# SPEED-CONTROLER.net
KiCad netlist of a schematic drawn in Altium Designer
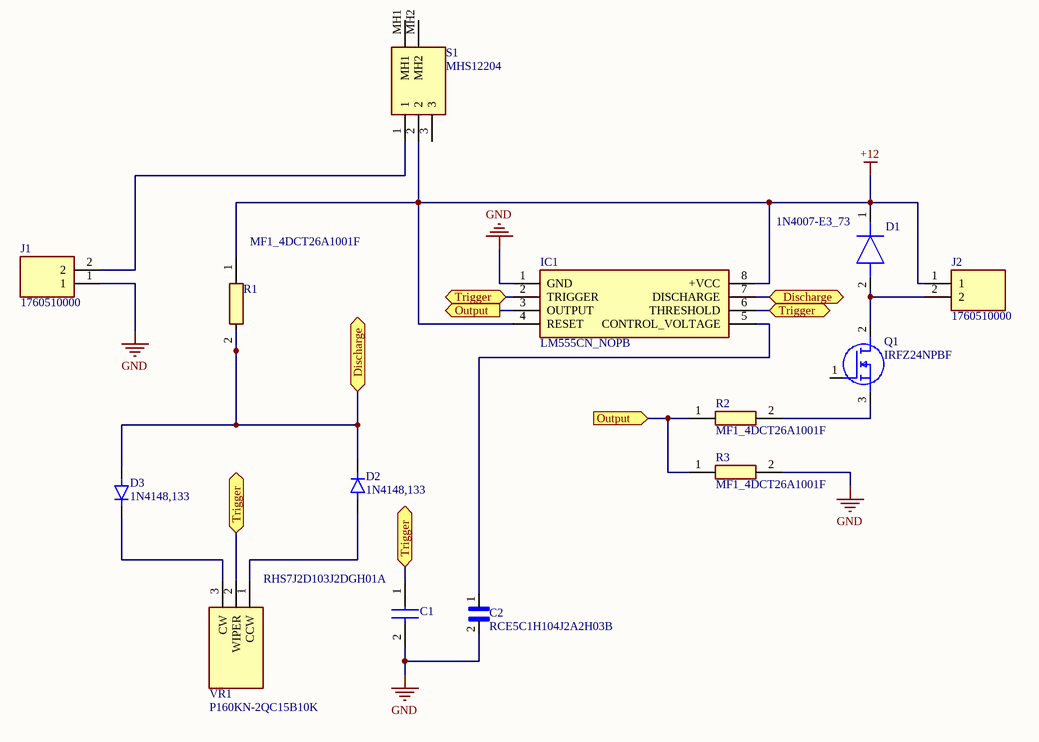
[diagram p0: SPEED-CONTROLER.SchDoc]

(export (version "E")
  (design (tool "Eeschema 10.0.6"))
  (components
    (comp (ref "C1")
      (value "RHS7J2D103J2DGH01A")
      (footprint "SamacSys:RHS7J2D103J2DGH01A")
      (description "Capacitor")
      (fields (field (name "MOUSER PART NUMBER") "81-RHS7J2D103J2DGH1A"))
      (libsource (lib "*") (part "RHS7J2D103J2DGH01A"))
    )
    (comp (ref "C2")
      (value "RCE5C1H104J2A2H03B")
      (footprint "CAP_RCE5C1H104J2A2H03B")
      (description "Multilayer Ceramic Capacitors MLCC - Leaded")
      (libsource (lib "RCE5C1H104J2A2H03B") (part "RCE5C1H104J2A2H03B"))
    )
    (comp (ref "D1")
      (value "1N4007-E3_73")
      (footprint "SamacSys:DIOAD1405W86L465D235")
      (description "Diode")
      (fields
        (field (name "MANUFACTURER_PART_NUMBER") "1N4007-E3/73")
        (field (name "MOUSER PART NUMBER") "625-1N4007-E3/73")
      )
      (libsource (lib "*") (part "1N4007-E3_73"))
    )
    (comp (ref "D2")
      (value "1N4148,133")
      (footprint "DIOAD753W49L380D172B")
      (description "Diode Standard 75V 200mA Surface Mount SOD-523F")
      (fields (field (name "MF") "ON Semiconductor") (field (name "MP") "1N4148"))
      (libsource (lib "1N4148") (part "1N4148"))
    )
    (comp (ref "D3")
      (value "1N4148,133")
      (footprint "DIOAD753W49L380D172B")
      (description "Diode Standard 75V 200mA Surface Mount SOD-523F")
      (fields (field (name "MF") "ON Semiconductor") (field (name "MP") "1N4148"))
      (libsource (lib "1N4148") (part "1N4148"))
    )
    (comp (ref "IC1")
      (value "LM555CN_NOPB")
      (footprint "SamacSys:DIP794W53P254L959H508Q8N")
      (description "Integrated Circuit")
      (fields
        (field (name "MANUFACTURER_PART_NUMBER") "LM555CN/NOPB")
        (field (name "MOUSER PART NUMBER") "926-LM555CN/NOPB")
      )
      (libsource (lib "*") (part "LM555CN_NOPB"))
    )
    (comp (ref "J1")
      (value "1760510000")
      (footprint "SamacSys:1760510000")
      (description "Connector")
      (fields (field (name "MOUSER PART NUMBER") "470-1760510000"))
      (libsource (lib "") (part "1760510000_1"))
    )
    (comp (ref "J2")
      (value "1760510000")
      (footprint "SamacSys:1760510000")
      (description "Connector")
      (fields (field (name "MOUSER PART NUMBER") "470-1760510000"))
      (libsource (lib "SamacSys") (part "1760510000"))
    )
    (comp (ref "Q1")
      (value "IRFZ24NPBF")
      (footprint "SamacSys:TO254P469X1042X1967-3P")
      (description "MOSFET (N-Channel)")
      (fields (field (name "MOUSER PART NUMBER") "942-IRFZ24NPBF"))
      (libsource (lib "*") (part "IRFZ24NPBF"))
    )
    (comp (ref "R1")
      (value "MF1_4DCT26A1001F")
      (footprint "SamacSys:RESAD1630W60L710D230")
      (description "Resistor")
      (fields
        (field (name "MANUFACTURER_PART_NUMBER") "MF1/4DCT26A1001F")
        (field (name "MOUSER PART NUMBER") "660-MF1/4DCT26A1001F")
      )
      (libsource (lib "*") (part "MF1_4DCT26A1001F"))
    )
    (comp (ref "R2")
      (value "MF1_4DCT26A1001F")
      (footprint "SamacSys:RESAD1630W60L710D230")
      (description "Resistor")
      (fields
        (field (name "MANUFACTURER_PART_NUMBER") "MF1/4DCT26A1001F")
        (field (name "MOUSER PART NUMBER") "660-MF1/4DCT26A1001F")
      )
      (libsource (lib "") (part "MF1_4DCT26A1001F_1"))
    )
    (comp (ref "R3")
      (value "MF1_4DCT26A1001F")
      (footprint "SamacSys:RESAD1630W60L710D230")
      (description "Resistor")
      (fields
        (field (name "MANUFACTURER_PART_NUMBER") "MF1/4DCT26A1001F")
        (field (name "MOUSER PART NUMBER") "660-MF1/4DCT26A1001F")
      )
      (libsource (lib "") (part "MF1_4DCT26A1001F_1"))
    )
    (comp (ref "S1")
      (value "MHS12204")
      (footprint "SamacSys:MHS12204")
      (description "Switch")
      (fields (field (name "MOUSER PART NUMBER") "506-MHS12204"))
      (libsource (lib "*") (part "MHS12204"))
    )
    (comp (ref "VR1")
      (value "P160KN-2QC15B10K")
      (footprint "SamacSys:P160KN2QC15B10K")
      (description "Variable Resistor")
      (fields (field (name "MOUSER PART NUMBER") "374-P160KN-2QC15B10K"))
      (libsource (lib "*") (part "P160KN-2QC15B10K"))
    )
  )
  (nets
    (net (code "1") (name "+12") (class "Default")
      (node (ref "D1") (pin "1") (pinfunction "K_1") (pintype "passive"))
      (node (ref "IC1") (pin "4") (pinfunction "RESET_4") (pintype "passive"))
      (node (ref "IC1") (pin "8") (pinfunction "+VCC_8") (pintype "passive"))
      (node (ref "J2") (pin "1") (pinfunction "1_1") (pintype "passive"))
      (node (ref "R1") (pin "1") (pinfunction "1_1") (pintype "passive"))
      (node (ref "S1") (pin "2") (pinfunction "2_2") (pintype "passive"))
    )
    (net (code "2") (name "/Discharge") (class "Default")
      (node (ref "D2") (pin "K") (pinfunction "K_K") (pintype "passive"))
      (node (ref "D3") (pin "A") (pinfunction "A_A") (pintype "passive"))
      (node (ref "IC1") (pin "7") (pinfunction "DISCHARGE_7") (pintype "passive"))
      (node (ref "R1") (pin "2") (pinfunction "2_2") (pintype "passive"))
    )
    (net (code "3") (name "/Output") (class "Default")
      (node (ref "IC1") (pin "3") (pinfunction "OUTPUT_3") (pintype "passive"))
      (node (ref "R2") (pin "1") (pinfunction "1_1") (pintype "passive"))
      (node (ref "R3") (pin "1") (pinfunction "1_1") (pintype "passive"))
    )
    (net (code "4") (name "/Trigger") (class "Default")
      (node (ref "C1") (pin "1") (pinfunction "1_1") (pintype "passive"))
      (node (ref "IC1") (pin "2") (pinfunction "TRIGGER_2") (pintype "passive"))
      (node (ref "IC1") (pin "6") (pinfunction "THRESHOLD_6") (pintype "passive"))
      (node (ref "VR1") (pin "2") (pinfunction "WIPER_2") (pintype "passive"))
    )
    (net (code "5") (name "GND") (class "Default")
      (node (ref "C1") (pin "2") (pinfunction "2_2") (pintype "passive"))
      (node (ref "C2") (pin "2") (pinfunction "2_2") (pintype "passive"))
      (node (ref "IC1") (pin "1") (pinfunction "GND_1") (pintype "passive"))
      (node (ref "J1") (pin "1") (pinfunction "1_1") (pintype "passive"))
      (node (ref "R3") (pin "2") (pinfunction "2_2") (pintype "passive"))
    )
    (net (code "6") (name "Net-(D1-A)") (class "Default")
      (node (ref "D1") (pin "2") (pinfunction "A_2") (pintype "passive"))
      (node (ref "J2") (pin "2") (pinfunction "2_2") (pintype "passive"))
      (node (ref "Q1") (pin "2") (pinfunction "D_2") (pintype "passive"))
    )
    (net (code "7") (name "Net-(IC1-CONTROL_VOLTAGE)") (class "Default")
      (node (ref "C2") (pin "1") (pinfunction "1_1") (pintype "passive"))
      (node (ref "IC1") (pin "5") (pinfunction "CONTROL_VOLTAGE_5") (pintype "passive"))
    )
    (net (code "8") (name "Net-(J1-Pad2)") (class "Default")
      (node (ref "J1") (pin "2") (pinfunction "2_2") (pintype "passive"))
      (node (ref "S1") (pin "1") (pinfunction "1_1") (pintype "passive"))
    )
    (net (code "9") (name "Net-(Q1-S)") (class "Default")
      (node (ref "Q1") (pin "3") (pinfunction "S_3") (pintype "passive"))
      (node (ref "R2") (pin "2") (pinfunction "2_2") (pintype "passive"))
    )
    (net (code "10") (name "Net-(VR1-CCW)") (class "Default")
      (node (ref "D2") (pin "A") (pinfunction "A_A") (pintype "passive"))
      (node (ref "VR1") (pin "1") (pinfunction "CCW_1") (pintype "passive"))
    )
    (net (code "11") (name "Net-(VR1-CW)") (class "Default")
      (node (ref "D3") (pin "K") (pinfunction "K_K") (pintype "passive"))
      (node (ref "VR1") (pin "3") (pinfunction "CW_3") (pintype "passive"))
    )
    (net (code "12") (name "unconnected-(Q1-G-Pad1)") (class "Default")
      (node (ref "Q1") (pin "1") (pinfunction "G_1") (pintype "passive"))
    )
    (net (code "13") (name "unconnected-(S1-Pad3)") (class "Default")
      (node (ref "S1") (pin "3") (pinfunction "3_3") (pintype "passive"))
    )
    (net (code "14") (name "unconnected-(S1-PadMH1)") (class "Default")
      (node (ref "S1") (pin "MH1") (pinfunction "MH1_MH1") (pintype "passive"))
    )
    (net (code "15") (name "unconnected-(S1-PadMH2)") (class "Default")
      (node (ref "S1") (pin "MH2") (pinfunction "MH2_MH2") (pintype "passive"))
    )
  )
)
